# POWER.net
KiCad netlist of a schematic drawn in Altium Designer
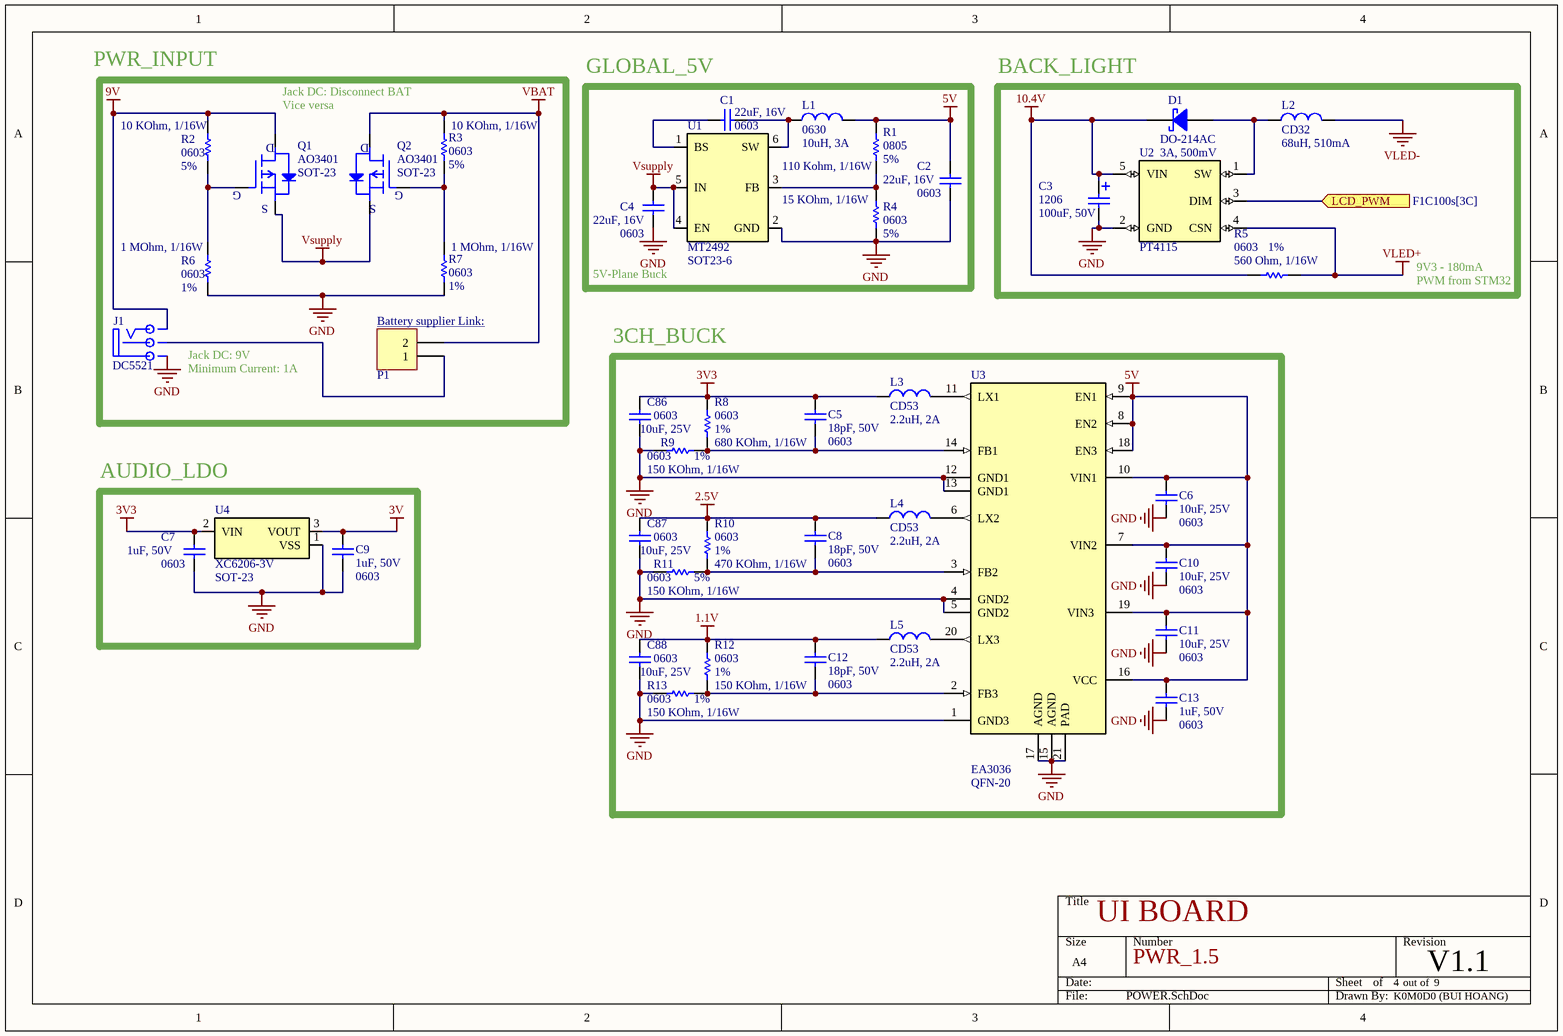
[diagram p0: POWER.SchDoc]

(export (version "E")
  (design (tool "Eeschema 10.0.6"))
  (components
    (comp (ref "C1")
      (value "22uF, 16V")
      (footprint "C_0603")
      (description "CAP_0603")
      (fields (field (name "PACKAGE") "0603"))
      (libsource (lib "DisplayLib") (part "CAP_0603"))
    )
    (comp (ref "C2")
      (value "22uF, 16V")
      (footprint "C_0603")
      (description "CAP_0603")
      (fields (field (name "PACKAGE") "0603"))
      (libsource (lib "DisplayLib") (part "CAP_0603"))
    )
    (comp (ref "C3")
      (value "100uF, 50V")
      (footprint "C_1206+")
      (description "CAP+1206")
      (fields (field (name "PACKAGE") "1206"))
      (libsource (lib "DisplayLib") (part "CAP+1206"))
    )
    (comp (ref "C4")
      (value "22uF, 16V")
      (footprint "C_0603")
      (description "CAP_0603")
      (fields (field (name "PACKAGE") "0603"))
      (libsource (lib "DisplayLib") (part "CAP_0603"))
    )
    (comp (ref "C5")
      (value "18pF, 50V")
      (footprint "C_0603")
      (description "CAP_0603")
      (fields (field (name "PACKAGE") "0603"))
      (libsource (lib "DisplayLib") (part "CAP_0603"))
    )
    (comp (ref "C6")
      (value "10uF, 25V")
      (footprint "C_0603")
      (description "CAP_0603")
      (fields (field (name "PACKAGE") "0603"))
      (libsource (lib "DisplayLib") (part "CAP_0603"))
    )
    (comp (ref "C7")
      (value "1uF, 50V")
      (footprint "C_0603")
      (description "CAP_0603")
      (fields (field (name "PACKAGE") "0603"))
      (libsource (lib "DisplayLib") (part "CAP_0603"))
    )
    (comp (ref "C8")
      (value "18pF, 50V")
      (footprint "C_0603")
      (description "CAP_0603")
      (fields (field (name "PACKAGE") "0603"))
      (libsource (lib "DisplayLib") (part "CAP_0603"))
    )
    (comp (ref "C9")
      (value "1uF, 50V")
      (footprint "C_0603")
      (description "CAP_0603")
      (fields (field (name "PACKAGE") "0603"))
      (libsource (lib "DisplayLib") (part "CAP_0603"))
    )
    (comp (ref "C10")
      (value "10uF, 25V")
      (footprint "C_0603")
      (description "CAP_0603")
      (fields (field (name "PACKAGE") "0603"))
      (libsource (lib "DisplayLib") (part "CAP_0603"))
    )
    (comp (ref "C11")
      (value "10uF, 25V")
      (footprint "C_0603")
      (description "CAP_0603")
      (fields (field (name "PACKAGE") "0603"))
      (libsource (lib "DisplayLib") (part "CAP_0603"))
    )
    (comp (ref "C12")
      (value "18pF, 50V")
      (footprint "C_0603")
      (description "CAP_0603")
      (fields (field (name "PACKAGE") "0603"))
      (libsource (lib "DisplayLib") (part "CAP_0603"))
    )
    (comp (ref "C13")
      (value "1uF, 50V")
      (footprint "C_0603")
      (description "CAP_0603")
      (fields (field (name "PACKAGE") "0603"))
      (libsource (lib "DisplayLib") (part "CAP_0603"))
    )
    (comp (ref "C86")
      (value "10uF, 25V")
      (footprint "C_0603")
      (description "CAP_0603")
      (fields (field (name "PACKAGE") "0603"))
      (libsource (lib "DisplayLib") (part "CAP_0603"))
    )
    (comp (ref "C87")
      (value "10uF, 25V")
      (footprint "C_0603")
      (description "CAP_0603")
      (fields (field (name "PACKAGE") "0603"))
      (libsource (lib "DisplayLib") (part "CAP_0603"))
    )
    (comp (ref "C88")
      (value "10uF, 25V")
      (footprint "C_0603")
      (description "CAP_0603")
      (fields (field (name "PACKAGE") "0603"))
      (libsource (lib "DisplayLib") (part "CAP_0603"))
    )
    (comp (ref "D1")
      (value "3A, 500mV")
      (footprint "PKG_SMA (DO-214AC)")
      (description "SS34")
      (fields (field (name "PACKAGE") "DO-214AC"))
      (libsource (lib "DisplayLib") (part "SCHOTTKY"))
    )
    (comp (ref "J1")
      (value "DC5521")
      (footprint "CONN_DC5521")
      (description "Jack DC")
      (libsource (lib "DisplayLib") (part "DC5521"))
    )
    (comp (ref "L1")
      (value "10uH, 3A")
      (footprint "COIL_74")
      (description "IN_0630")
      (fields (field (name "PACKAGE") "0630"))
      (libsource (lib "DisplayLib") (part "IN_0630"))
    )
    (comp (ref "L2")
      (value "68uH, 510mA")
      (footprint "COIL_CD32")
      (description "IN_CD32")
      (fields (field (name "PACKAGE") "CD32"))
      (libsource (lib "DisplayLib") (part "IN_CD32"))
    )
    (comp (ref "L3")
      (value "2.2uH, 2A")
      (footprint "COIL_CD53")
      (description "IN_CD53")
      (fields (field (name "PACKAGE") "CD53"))
      (libsource (lib "DisplayLib") (part "IN_CD53"))
    )
    (comp (ref "L4")
      (value "2.2uH, 2A")
      (footprint "COIL_CD53")
      (description "IN_CD53")
      (fields (field (name "PACKAGE") "CD53"))
      (libsource (lib "DisplayLib") (part "IN_CD53"))
    )
    (comp (ref "L5")
      (value "2.2uH, 2A")
      (footprint "COIL_CD53")
      (description "IN_CD53")
      (fields (field (name "PACKAGE") "CD53"))
      (libsource (lib "DisplayLib") (part "IN_CD53"))
    )
    (comp (ref "P1")
      (value "Header 2")
      (footprint "JP2")
      (description "Header, 2-Pin")
      (fields (field (name "PUBLISHER") "Altium Limited"))
      (libsource (lib "PIF_Library") (part "Header 2"))
    )
    (comp (ref "Q1")
      (value "AO3401")
      (footprint "PKG_SOT-23")
      (description "P-Channel 30 V 4A (Ta) 1.4W (Ta) Surface Mount SOT-23-3")
      (fields (field (name "PACKAGE") "SOT-23"))
      (libsource (lib "DisplayLib") (part "AO3401"))
    )
    (comp (ref "Q2")
      (value "AO3401")
      (footprint "PKG_SOT-23")
      (description "P-Channel 30 V 4A (Ta) 1.4W (Ta) Surface Mount SOT-23-3")
      (fields (field (name "PACKAGE") "SOT-23"))
      (libsource (lib "DisplayLib") (part "AO3401"))
    )
    (comp (ref "R1")
      (value "110 Kohm, 1/16W")
      (footprint "R_0805")
      (description "RES_0805")
      (fields (field (name "PACKAGE") "0805") (field (name "ACC") "5%"))
      (libsource (lib "DisplayLib") (part "RES_0805"))
    )
    (comp (ref "R2")
      (value "10 KOhm, 1/16W")
      (footprint "R_0603")
      (description "RES_0603")
      (fields (field (name "PACKAGE") "0603") (field (name "ACC") "5%"))
      (libsource (lib "DisplayLib") (part "RES_0603"))
    )
    (comp (ref "R3")
      (value "10 KOhm, 1/16W")
      (footprint "R_0603")
      (description "RES_0603")
      (fields (field (name "PACKAGE") "0603") (field (name "ACC") "5%"))
      (libsource (lib "DisplayLib") (part "RES_0603"))
    )
    (comp (ref "R4")
      (value "15 KOhm, 1/16W")
      (footprint "R_0603")
      (description "RES_0603")
      (fields (field (name "PACKAGE") "0603") (field (name "ACC") "5%"))
      (libsource (lib "DisplayLib") (part "RES_0603"))
    )
    (comp (ref "R5")
      (value "560 Ohm, 1/16W")
      (footprint "R_0603")
      (description "RES_0603")
      (fields (field (name "PACKAGE") "0603") (field (name "ACC") "1%"))
      (libsource (lib "DisplayLib") (part "RES_0603"))
    )
    (comp (ref "R6")
      (value "1 MOhm, 1/16W")
      (footprint "R_0603")
      (description "RES_0603")
      (fields (field (name "PACKAGE") "0603") (field (name "ACC") "1%"))
      (libsource (lib "DisplayLib") (part "RES_0603"))
    )
    (comp (ref "R7")
      (value "1 MOhm, 1/16W")
      (footprint "R_0603")
      (description "RES_0603")
      (fields (field (name "PACKAGE") "0603") (field (name "ACC") "1%"))
      (libsource (lib "DisplayLib") (part "RES_0603"))
    )
    (comp (ref "R8")
      (value "680 KOhm, 1/16W")
      (footprint "R_0603")
      (description "RES_0603")
      (fields (field (name "PACKAGE") "0603") (field (name "ACC") "1%"))
      (libsource (lib "DisplayLib") (part "RES_0603"))
    )
    (comp (ref "R9")
      (value "150 KOhm, 1/16W")
      (footprint "R_0603")
      (description "RES_0603")
      (fields (field (name "PACKAGE") "0603") (field (name "ACC") "1%"))
      (libsource (lib "DisplayLib") (part "RES_0603"))
    )
    (comp (ref "R10")
      (value "470 KOhm, 1/16W")
      (footprint "R_0603")
      (description "RES_0603")
      (fields (field (name "PACKAGE") "0603") (field (name "ACC") "1%"))
      (libsource (lib "DisplayLib") (part "RES_0603"))
    )
    (comp (ref "R11")
      (value "150 KOhm, 1/16W")
      (footprint "R_0603")
      (description "RES_0603")
      (fields (field (name "PACKAGE") "0603") (field (name "ACC") "5%"))
      (libsource (lib "DisplayLib") (part "RES_0603"))
    )
    (comp (ref "R12")
      (value "150 KOhm, 1/16W")
      (footprint "R_0603")
      (description "RES_0603")
      (fields (field (name "PACKAGE") "0603") (field (name "ACC") "1%"))
      (libsource (lib "DisplayLib") (part "RES_0603"))
    )
    (comp (ref "R13")
      (value "150 KOhm, 1/16W")
      (footprint "R_0603")
      (description "RES_0603")
      (fields (field (name "PACKAGE") "0603") (field (name "ACC") "1%"))
      (libsource (lib "DisplayLib") (part "RES_0603"))
    )
    (comp (ref "U1")
      (value "MT2492")
      (footprint "PKG-SOT23-6")
      (description "600KHz, 16V，2A Synchronous\r\nStep-Down Converter")
      (fields (field (name "PACKAGE") "SOT23-6"))
      (libsource (lib "DisplayLib") (part "MT2492"))
    )
    (comp (ref "U2")
      (value "PT4115")
      (footprint "PKG_SOT-89-5")
      (description "0V, 1.2A Step-down High Brightness\r\nLED Driver with 5000:1 Dimming")
      (libsource (lib "DisplayLib") (part "PT4115"))
    )
    (comp (ref "U3")
      (value "EA3036")
      (footprint "PKG_QFN-20")
      (description "3CH power management IC for applications powered by one Li-Ion battery or a DC 5V adapter.")
      (fields (field (name "PACKAGE") "QFN-20"))
      (libsource (lib "DisplayLib") (part "EA3036"))
    )
    (comp (ref "U4")
      (value "XC6206-3V")
      (footprint "PKG_SOT-23")
      (description "P-Channel 30 V 4A (Ta) 1.4W (Ta) Surface Mount SOT-23-3")
      (fields (field (name "PACKAGE") "SOT-23"))
      (libsource (lib "DisplayLib") (part "XC6206-2.5V"))
    )
  )
  (nets
    (net (code "1") (name "/LCD_PWM") (class "Default")
      (node (ref "U2") (pin "3") (pinfunction "DIM_3") (pintype "bidirectional"))
    )
    (net (code "2") (name "1.1V") (class "Default")
      (node (ref "C12") (pin "2") (pinfunction "2_2") (pintype "passive"))
      (node (ref "C88") (pin "2") (pinfunction "2_2") (pintype "passive"))
      (node (ref "L5") (pin "1") (pinfunction "1_1") (pintype "passive"))
      (node (ref "R12") (pin "2") (pinfunction "2_2") (pintype "passive"))
    )
    (net (code "3") (name "2.5V") (class "Default")
      (node (ref "C8") (pin "2") (pinfunction "2_2") (pintype "passive"))
      (node (ref "C87") (pin "2") (pinfunction "2_2") (pintype "passive"))
      (node (ref "L4") (pin "1") (pinfunction "1_1") (pintype "passive"))
      (node (ref "R10") (pin "2") (pinfunction "2_2") (pintype "passive"))
    )
    (net (code "4") (name "3V") (class "Default")
      (node (ref "C9") (pin "2") (pinfunction "2_2") (pintype "passive"))
      (node (ref "U4") (pin "3") (pinfunction "VOUT_3") (pintype "passive"))
    )
    (net (code "5") (name "3V3") (class "Default")
      (node (ref "C5") (pin "2") (pinfunction "2_2") (pintype "passive"))
      (node (ref "C7") (pin "2") (pinfunction "2_2") (pintype "passive"))
      (node (ref "C86") (pin "2") (pinfunction "2_2") (pintype "passive"))
      (node (ref "L3") (pin "1") (pinfunction "1_1") (pintype "passive"))
      (node (ref "R8") (pin "2") (pinfunction "2_2") (pintype "passive"))
      (node (ref "U4") (pin "2") (pinfunction "VIN_2") (pintype "passive"))
    )
    (net (code "6") (name "5V") (class "Default")
      (node (ref "C10") (pin "2") (pinfunction "2_2") (pintype "passive"))
      (node (ref "C11") (pin "2") (pinfunction "2_2") (pintype "passive"))
      (node (ref "C13") (pin "2") (pinfunction "2_2") (pintype "passive"))
      (node (ref "C2") (pin "2") (pinfunction "2_2") (pintype "passive"))
      (node (ref "C6") (pin "2") (pinfunction "2_2") (pintype "passive"))
      (node (ref "L1") (pin "2") (pinfunction "2_2") (pintype "passive"))
      (node (ref "R1") (pin "2") (pinfunction "2_2") (pintype "passive"))
      (node (ref "U3") (pin "10") (pinfunction "VIN1_10") (pintype "power_in"))
      (node (ref "U3") (pin "16") (pinfunction "VCC_16") (pintype "power_in"))
      (node (ref "U3") (pin "18") (pinfunction "EN3_18") (pintype "input"))
      (node (ref "U3") (pin "19") (pinfunction "VIN3_19") (pintype "power_in"))
      (node (ref "U3") (pin "7") (pinfunction "VIN2_7") (pintype "power_in"))
      (node (ref "U3") (pin "8") (pinfunction "EN2_8") (pintype "input"))
      (node (ref "U3") (pin "9") (pinfunction "EN1_9") (pintype "input"))
    )
    (net (code "7") (name "9V") (class "Default")
      (node (ref "J1") (pin "1") (pinfunction "DC_1") (pintype "power_in"))
      (node (ref "Q1") (pin "3") (pinfunction "D_3") (pintype "passive"))
      (node (ref "R2") (pin "2") (pinfunction "2_2") (pintype "passive"))
    )
    (net (code "8") (name "10.4V") (class "Default")
      (node (ref "C3") (pin "2") (pinfunction "2_2") (pintype "passive"))
      (node (ref "D1") (pin "1") (pinfunction "K_1") (pintype "passive"))
      (node (ref "R5") (pin "2") (pinfunction "2_2") (pintype "passive"))
      (node (ref "U2") (pin "5") (pinfunction "VIN_5") (pintype "bidirectional"))
    )
    (net (code "9") (name "GND") (class "Default")
      (node (ref "C10") (pin "1") (pinfunction "1_1") (pintype "passive"))
      (node (ref "C11") (pin "1") (pinfunction "1_1") (pintype "passive"))
      (node (ref "C13") (pin "1") (pinfunction "1_1") (pintype "passive"))
      (node (ref "C2") (pin "1") (pinfunction "1_1") (pintype "passive"))
      (node (ref "C3") (pin "1") (pinfunction "1_1") (pintype "passive"))
      (node (ref "C4") (pin "2") (pinfunction "2_2") (pintype "passive"))
      (node (ref "C6") (pin "1") (pinfunction "1_1") (pintype "passive"))
      (node (ref "C7") (pin "1") (pinfunction "1_1") (pintype "passive"))
      (node (ref "C86") (pin "1") (pinfunction "1_1") (pintype "passive"))
      (node (ref "C87") (pin "1") (pinfunction "1_1") (pintype "passive"))
      (node (ref "C88") (pin "1") (pinfunction "1_1") (pintype "passive"))
      (node (ref "C9") (pin "1") (pinfunction "1_1") (pintype "passive"))
      (node (ref "J1") (pin "2") (pinfunction "GND_2") (pintype "power_in"))
      (node (ref "R11") (pin "1") (pinfunction "1_1") (pintype "passive"))
      (node (ref "R13") (pin "1") (pinfunction "1_1") (pintype "passive"))
      (node (ref "R4") (pin "1") (pinfunction "1_1") (pintype "passive"))
      (node (ref "R6") (pin "1") (pinfunction "1_1") (pintype "passive"))
      (node (ref "R7") (pin "1") (pinfunction "1_1") (pintype "passive"))
      (node (ref "R9") (pin "1") (pinfunction "1_1") (pintype "passive"))
      (node (ref "U1") (pin "2") (pinfunction "GND_2") (pintype "passive"))
      (node (ref "U2") (pin "2") (pinfunction "GND_2") (pintype "bidirectional"))
      (node (ref "U3") (pin "1") (pinfunction "GND3_1") (pintype "power_in"))
      (node (ref "U3") (pin "12") (pinfunction "GND1_12") (pintype "power_in"))
      (node (ref "U3") (pin "13") (pinfunction "GND1_13") (pintype "power_in"))
      (node (ref "U3") (pin "15") (pinfunction "AGND_15") (pintype "power_in"))
      (node (ref "U3") (pin "17") (pinfunction "AGND_17") (pintype "power_in"))
      (node (ref "U3") (pin "21") (pinfunction "PAD_21") (pintype "power_in"))
      (node (ref "U3") (pin "4") (pinfunction "GND2_4") (pintype "power_in"))
      (node (ref "U3") (pin "5") (pinfunction "GND2_5") (pintype "power_in"))
      (node (ref "U4") (pin "1") (pinfunction "VSS_1") (pintype "power_in"))
    )
    (net (code "10") (name "Net-(D1-A)") (class "Default")
      (node (ref "D1") (pin "2") (pinfunction "A_2") (pintype "passive"))
      (node (ref "L2") (pin "1") (pinfunction "1_1") (pintype "passive"))
      (node (ref "U2") (pin "1") (pinfunction "SW_1") (pintype "bidirectional"))
    )
    (net (code "11") (name "Net-(J1-SW)") (class "Default")
      (node (ref "J1") (pin "3") (pinfunction "SW_3") (pintype "passive"))
      (node (ref "P1") (pin "1") (pinfunction "1_1") (pintype "passive"))
    )
    (net (code "12") (name "Net-(Q1-G)") (class "Default")
      (node (ref "Q1") (pin "1") (pinfunction "G_1") (pintype "passive"))
      (node (ref "R2") (pin "1") (pinfunction "1_1") (pintype "passive"))
      (node (ref "R6") (pin "2") (pinfunction "2_2") (pintype "passive"))
    )
    (net (code "13") (name "Net-(Q2-G)") (class "Default")
      (node (ref "Q2") (pin "1") (pinfunction "G_1") (pintype "passive"))
      (node (ref "R3") (pin "1") (pinfunction "1_1") (pintype "passive"))
      (node (ref "R7") (pin "2") (pinfunction "2_2") (pintype "passive"))
    )
    (net (code "14") (name "Net-(U1-BS)") (class "Default")
      (node (ref "C1") (pin "2") (pinfunction "2_2") (pintype "passive"))
      (node (ref "U1") (pin "1") (pinfunction "BS_1") (pintype "passive"))
    )
    (net (code "15") (name "Net-(U1-FB)") (class "Default")
      (node (ref "R1") (pin "1") (pinfunction "1_1") (pintype "passive"))
      (node (ref "R4") (pin "2") (pinfunction "2_2") (pintype "passive"))
      (node (ref "U1") (pin "3") (pinfunction "FB_3") (pintype "passive"))
    )
    (net (code "16") (name "Net-(U1-SW)") (class "Default")
      (node (ref "C1") (pin "1") (pinfunction "1_1") (pintype "passive"))
      (node (ref "L1") (pin "1") (pinfunction "1_1") (pintype "passive"))
      (node (ref "U1") (pin "6") (pinfunction "SW_6") (pintype "passive"))
    )
    (net (code "17") (name "Net-(U3-FB1)") (class "Default")
      (node (ref "C5") (pin "1") (pinfunction "1_1") (pintype "passive"))
      (node (ref "R8") (pin "1") (pinfunction "1_1") (pintype "passive"))
      (node (ref "R9") (pin "2") (pinfunction "2_2") (pintype "passive"))
      (node (ref "U3") (pin "14") (pinfunction "FB1_14") (pintype "input"))
    )
    (net (code "18") (name "Net-(U3-FB2)") (class "Default")
      (node (ref "C8") (pin "1") (pinfunction "1_1") (pintype "passive"))
      (node (ref "R10") (pin "1") (pinfunction "1_1") (pintype "passive"))
      (node (ref "R11") (pin "2") (pinfunction "2_2") (pintype "passive"))
      (node (ref "U3") (pin "3") (pinfunction "FB2_3") (pintype "input"))
    )
    (net (code "19") (name "Net-(U3-FB3)") (class "Default")
      (node (ref "C12") (pin "1") (pinfunction "1_1") (pintype "passive"))
      (node (ref "R12") (pin "1") (pinfunction "1_1") (pintype "passive"))
      (node (ref "R13") (pin "2") (pinfunction "2_2") (pintype "passive"))
      (node (ref "U3") (pin "2") (pinfunction "FB3_2") (pintype "input"))
    )
    (net (code "20") (name "Net-(U3-LX1)") (class "Default")
      (node (ref "L3") (pin "2") (pinfunction "2_2") (pintype "passive"))
      (node (ref "U3") (pin "11") (pinfunction "LX1_11") (pintype "output"))
    )
    (net (code "21") (name "Net-(U3-LX2)") (class "Default")
      (node (ref "L4") (pin "2") (pinfunction "2_2") (pintype "passive"))
      (node (ref "U3") (pin "6") (pinfunction "LX2_6") (pintype "output"))
    )
    (net (code "22") (name "Net-(U3-LX3)") (class "Default")
      (node (ref "L5") (pin "2") (pinfunction "2_2") (pintype "passive"))
      (node (ref "U3") (pin "20") (pinfunction "LX3_20") (pintype "output"))
    )
    (net (code "23") (name "VBAT") (class "Default")
      (node (ref "P1") (pin "2") (pinfunction "2_2") (pintype "passive"))
      (node (ref "Q2") (pin "3") (pinfunction "D_3") (pintype "passive"))
      (node (ref "R3") (pin "2") (pinfunction "2_2") (pintype "passive"))
    )
    (net (code "24") (name "VLED+") (class "Default")
      (node (ref "R5") (pin "1") (pinfunction "1_1") (pintype "passive"))
      (node (ref "U2") (pin "4") (pinfunction "CSN_4") (pintype "bidirectional"))
    )
    (net (code "25") (name "VLED-") (class "Default")
      (node (ref "L2") (pin "2") (pinfunction "2_2") (pintype "passive"))
    )
    (net (code "26") (name "Vsupply") (class "Default")
      (node (ref "C4") (pin "1") (pinfunction "1_1") (pintype "passive"))
      (node (ref "Q1") (pin "2") (pinfunction "S_2") (pintype "passive"))
      (node (ref "Q2") (pin "2") (pinfunction "S_2") (pintype "passive"))
      (node (ref "U1") (pin "4") (pinfunction "EN_4") (pintype "passive"))
      (node (ref "U1") (pin "5") (pinfunction "IN_5") (pintype "passive"))
    )
  )
)
